# Communication.net
KiCad netlist of a schematic drawn in Altium Designer
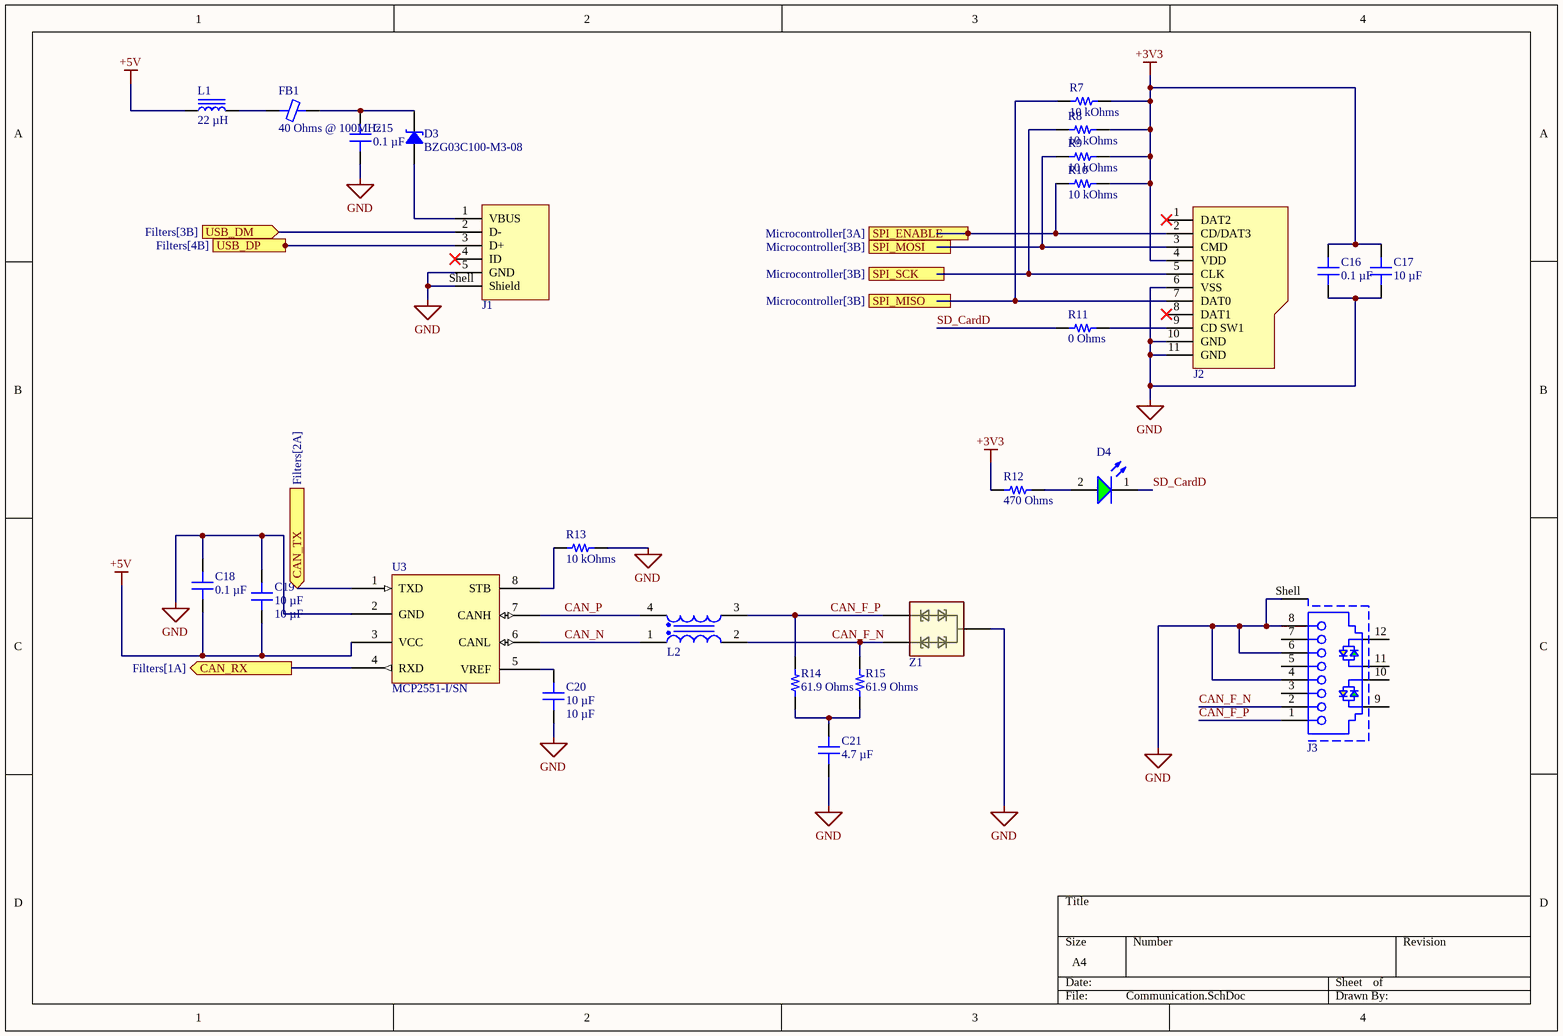
[diagram p0: Communication.SchDoc]

(export (version "E")
  (design (tool "Eeschema 10.0.6"))
  (components
    (comp (ref "C15")
      (value "0.1 µF")
      (footprint "CAP 0805_2012")
      (description "CAP CER 0.1UF 50V X7R 0805")
      (fields (field (name "PART NUMBER") "CC0805MRX7R9BB104") (field (name "MANUFACTURER") "Yageo"))
      (libsource (lib "Celestial Altium Library - altium_library (2)") (part "Capacitor"))
    )
    (comp (ref "C16")
      (value "0.1 µF")
      (footprint "CAP 0805_2012")
      (description "CAP CER 0.1UF 50V X7R 0805")
      (fields (field (name "PART NUMBER") "CC0805MRX7R9BB104") (field (name "MANUFACTURER") "Yageo"))
      (libsource (lib "Celestial Altium Library - altium_library (2)") (part "Capacitor"))
    )
    (comp (ref "C17")
      (value "10 µF")
      (footprint "CAP 0805_2012")
      (description "CAP CER 10UF 10V X7S 0805")
      (fields
        (field (name "PART NUMBER") "CL21Y106KPQVPNE")
        (field (name "MANUFACTURER") "Samsung Electro-Mechanics")
      )
      (libsource (lib "Celestial Altium Library - altium_library (2)") (part "Capacitor"))
    )
    (comp (ref "C18")
      (value "0.1 µF")
      (footprint "CAP 0805_2012")
      (description "CAP CER 0.1UF 50V X7R 0805")
      (fields (field (name "PART NUMBER") "CC0805MRX7R9BB104") (field (name "MANUFACTURER") "Yageo"))
      (libsource (lib "Celestial Altium Library - altium_library (2)") (part "Capacitor"))
    )
    (comp (ref "C19")
      (value "10 µF")
      (footprint "CAP 0805_2012")
      (description "CAP CER 10UF 10V X7S 0805")
      (fields (field (name "PART NUMBER") "CL21Y106KPQVPNE") (field (name "ALTIUM_VALUE") "10 µF"))
      (libsource (lib "Celestial Altium Library - altium_library (2)") (part "Capacitor"))
    )
    (comp (ref "C20")
      (value "10 µF")
      (footprint "CAP 0805_2012")
      (description "CAP CER 10UF 10V X7S 0805")
      (fields (field (name "PART NUMBER") "CL21Y106KPQVPNE") (field (name "ALTIUM_VALUE") "10 µF"))
      (libsource (lib "Celestial Altium Library - altium_library (2)") (part "Capacitor"))
    )
    (comp (ref "C21")
      (value "4.7 µF")
      (footprint "CAP 0805_2012")
      (description "CAP CER 4.7UF 25V X7R 0805")
      (fields
        (field (name "PART NUMBER") "CL21B475KAFNNNE")
        (field (name "MANUFACTURER") "Samsung Electro-Mechanics")
      )
      (libsource (lib "Celestial Altium Library - altium_library (2)") (part "Capacitor"))
    )
    (comp (ref "D3")
      (value "BZG03C100-M3-08")
      (footprint "DO214AC SMA")
      (description "DIODE ZENER 100V 1.25W DO214AC")
      (fields
        (field (name "MANUFACTURER") "Vishay Semiconductor Diodes Division")
        (field (name "TOLERANCE") "±6%")
      )
      (libsource (lib "Celestial Altium Library - altium_library (2)") (part "Diode Zener"))
    )
    (comp (ref "D4")
      (value "Green, 3.2V, 140°")
      (footprint "WL-SMCW_0805_150080xx75000")
      (description "WL-SMCW Mono-color Chip LED Waterclear, size 0805, Green, 3.2V, 140°")
      (fields
        (field (name "MANUFACTURER PART NUMBER") "150080GS75000")
        (field (name "MANUFACTURER") "Wurth Elektronik")
      )
      (libsource (lib "WE - Optoelectronic Components") (part "LED_Green_2A-1K"))
    )
    (comp (ref "FB1")
      (value "40 Ohms @ 100MHz")
      (footprint "FER 0805_2012")
      (description "FERRITE BEAD 40 OHM 0805 1LN")
      (fields (field (name "PART NUMBER") "ILBB0805ER400V") (field (name "MANUFACTURER") "Vishay Dale"))
      (libsource (lib "Celestial Altium Library - altium_library (2)") (part "Ferrite Chip"))
    )
    (comp (ref "J1")
      (value "629105150521")
      (footprint "629105150521")
      (description "WR-COM Micro USB 2.0 SMT Type B Horizontal 5 Contacts High Current")
      (fields (field (name "MANUFACTURER") "Wurth Elektronik"))
      (libsource (lib "WE - Electromechanical Components") (part "Micro USB 2.0_Type B_Receptacle_1 Port"))
    )
    (comp (ref "J2")
      (value "693071030811")
      (footprint "693071030811")
      (description "WR-CRD Micro SD Card Connector Push & Push")
      (fields (field (name "MANUFACTURER") "Wurth Elektronik"))
      (libsource (lib "WE - Electromechanical Components") (part "693071030811"))
    )
    (comp (ref "J3")
      (value "615008142121")
      (footprint "615008142121")
      (description "WR-MJ Modular Jack THT Horizontal Shielded 8P8C Tab Up")
      (fields (field (name "MANUFACTURER") "Wurth Elektronik"))
      (libsource (lib "WE - Electromechanical Components") (part "8P8C - 1 Port - Shielded - Bipolar Y/G - 615008142121"))
    )
    (comp (ref "L1")
      (value "22 µH")
      (footprint "IND 0806_2016")
      (description "FIXED IND 22UH 310MA 1 OHM SMD")
      (fields (field (name "PART NUMBER") "LSQPB201616T220M") (field (name "MANUFACTURER") "Taiyo Yuden"))
      (libsource (lib "Celestial Altium Library - altium_library (2)") (part "Inductor"))
    )
    (comp (ref "L2")
      (value "5000Ohm")
      (footprint "WE-CNSW_1812")
      (description "WE-CNSW SMT Common Mode Line Filter, size 1812, 5000Ohm, 100uH, 60V")
      (fields
        (field (name "MANUFACTURER PART NUMBER") "744235101")
        (field (name "MANUFACTURER") "Wurth Elektronik")
      )
      (libsource (lib "WE - Passive Components") (part "WE-CNSW"))
    )
    (comp (ref "R7")
      (value "10 kOhms")
      (footprint "RES 0805_2012")
      (description "RES SMD 10K OHM 0.1% 1/4W 0805")
      (fields
        (field (name "PART NUMBER") "2176093-5")
        (field (name "MANUFACTURER") "TE Connectivity Passive Product")
      )
      (libsource (lib "Celestial Altium Library - altium_library (2)") (part "Resistor"))
    )
    (comp (ref "R8")
      (value "10 kOhms")
      (footprint "RES 0805_2012")
      (description "RES SMD 10K OHM 0.1% 1/4W 0805")
      (fields
        (field (name "PART NUMBER") "2176093-5")
        (field (name "MANUFACTURER") "TE Connectivity Passive Product")
      )
      (libsource (lib "Celestial Altium Library - altium_library (2)") (part "Resistor"))
    )
    (comp (ref "R9")
      (value "10 kOhms")
      (footprint "RES 0805_2012")
      (description "RES SMD 10K OHM 0.1% 1/4W 0805")
      (fields
        (field (name "PART NUMBER") "2176093-5")
        (field (name "MANUFACTURER") "TE Connectivity Passive Product")
      )
      (libsource (lib "Celestial Altium Library - altium_library (2)") (part "Resistor"))
    )
    (comp (ref "R10")
      (value "10 kOhms")
      (footprint "RES 0805_2012")
      (description "RES SMD 10K OHM 0.1% 1/4W 0805")
      (fields
        (field (name "PART NUMBER") "2176093-5")
        (field (name "MANUFACTURER") "TE Connectivity Passive Product")
      )
      (libsource (lib "Celestial Altium Library - altium_library (2)") (part "Resistor"))
    )
    (comp (ref "R11")
      (value "0 Ohms")
      (footprint "RES 0805_2012")
      (description "RES 0 OHM JUMPER 0805")
      (fields (field (name "PART NUMBER") "5107") (field (name "MANUFACTURER") "Keystone Electronics"))
      (libsource (lib "Celestial Altium Library - altium_library (2)") (part "Resistor"))
    )
    (comp (ref "R12")
      (value "470 Ohms")
      (footprint "RES 0805_2012")
      (description "3430 A2 1% 470R 100PPM 1K RL")
      (fields
        (field (name "PART NUMBER") "3430A2F470RTDF")
        (field (name "MANUFACTURER") "TE Connectivity Passive Product")
      )
      (libsource (lib "Celestial Altium Library - altium_library (2)") (part "Resistor"))
    )
    (comp (ref "R13")
      (value "10 kOhms")
      (footprint "RES 0805_2012")
      (description "RES SMD 10K OHM 0.1% 1/4W 0805")
      (fields
        (field (name "PART NUMBER") "2176093-5")
        (field (name "MANUFACTURER") "TE Connectivity Passive Product")
      )
      (libsource (lib "Celestial Altium Library - altium_library (2)") (part "Resistor"))
    )
    (comp (ref "R14")
      (value "61.9 Ohms")
      (footprint "RES 0805_2012")
      (description "RES SMD 61.9 OHM 0.1% 1/4W 0805")
      (fields
        (field (name "PART NUMBER") "2176091-4")
        (field (name "MANUFACTURER") "TE Connectivity Passive Product")
      )
      (libsource (lib "Celestial Altium Library - altium_library (2)") (part "Resistor"))
    )
    (comp (ref "R15")
      (value "61.9 Ohms")
      (footprint "RES 0805_2012")
      (description "RES SMD 61.9 OHM 0.1% 1/4W 0805")
      (fields
        (field (name "PART NUMBER") "2176091-4")
        (field (name "MANUFACTURER") "TE Connectivity Passive Product")
      )
      (libsource (lib "Celestial Altium Library - altium_library (2)") (part "Resistor"))
    )
    (comp (ref "U3")
      (value "MCP2551")
      (footprint "MCP2551T-I/SN")
      (description "MCP2551 CAN Transreciever 8Mbit/sn")
      (fields (field (name "SUPPLIER PART NUMBER 1") "MCP2551-I/SN"))
      (libsource (lib "Schlib1") (part "MCP2551"))
    )
    (comp (ref "Z1")
      (value "PESD2CAN,215")
      (footprint "SOT95P230X110-3N")
      (description "Zener Diode")
      (fields
        (field (name "MOUSER PART NUMBER") "771-PESD2CAN-T/R")
        (field (name "RS PART NUMBER") "0508462")
      )
      (libsource (lib "Schlib1") (part "PESD2CAN,215"))
    )
  )
  (nets
    (net (code "1") (name "+3V3") (class "Default")
      (node (ref "C16") (pin "2") (pinfunction "2_2") (pintype "passive"))
      (node (ref "C17") (pin "2") (pinfunction "2_2") (pintype "passive"))
      (node (ref "J2") (pin "4") (pinfunction "VDD_4") (pintype "passive"))
      (node (ref "R10") (pin "2") (pinfunction "2_2") (pintype "passive"))
      (node (ref "R12") (pin "1") (pinfunction "1_1") (pintype "passive"))
      (node (ref "R7") (pin "2") (pinfunction "2_2") (pintype "passive"))
      (node (ref "R8") (pin "2") (pinfunction "2_2") (pintype "passive"))
      (node (ref "R9") (pin "2") (pinfunction "2_2") (pintype "passive"))
    )
    (net (code "2") (name "+5V") (class "Default")
      (node (ref "C18") (pin "2") (pinfunction "2_2") (pintype "passive"))
      (node (ref "C19") (pin "1") (pinfunction "1_1") (pintype "passive"))
      (node (ref "L1") (pin "1") (pinfunction "1_1") (pintype "passive"))
      (node (ref "U3") (pin "3") (pinfunction "VCC_3") (pintype "passive"))
    )
    (net (code "3") (name "/CAN_F_N") (class "Default")
      (node (ref "J3") (pin "2") (pinfunction "2_2") (pintype "passive"))
      (node (ref "L2") (pin "2") (pinfunction "2_2") (pintype "passive"))
      (node (ref "R15") (pin "2") (pinfunction "2_2") (pintype "passive"))
      (node (ref "Z1") (pin "2") (pinfunction "2_2") (pintype "passive"))
    )
    (net (code "4") (name "/CAN_F_P") (class "Default")
      (node (ref "J3") (pin "1") (pinfunction "1_1") (pintype "passive"))
      (node (ref "L2") (pin "3") (pinfunction "3_3") (pintype "passive"))
      (node (ref "R14") (pin "2") (pinfunction "2_2") (pintype "passive"))
      (node (ref "Z1") (pin "1") (pinfunction "1_1") (pintype "passive"))
    )
    (net (code "5") (name "/CAN_N") (class "Default")
      (node (ref "L2") (pin "1") (pinfunction "1_1") (pintype "passive"))
      (node (ref "U3") (pin "6") (pinfunction "CANL_6") (pintype "bidirectional"))
    )
    (net (code "6") (name "/CAN_P") (class "Default")
      (node (ref "L2") (pin "4") (pinfunction "4_4") (pintype "passive"))
      (node (ref "U3") (pin "7") (pinfunction "CANH_7") (pintype "bidirectional"))
    )
    (net (code "7") (name "/CAN_RX") (class "Default")
      (node (ref "U3") (pin "4") (pinfunction "RXD_4") (pintype "output"))
    )
    (net (code "8") (name "/CAN_TX") (class "Default")
      (node (ref "U3") (pin "1") (pinfunction "TXD_1") (pintype "input"))
    )
    (net (code "9") (name "/SD_CardD") (class "Default")
      (node (ref "D4") (pin "1") (pinfunction "K_1") (pintype "passive"))
      (node (ref "R11") (pin "1") (pinfunction "1_1") (pintype "passive"))
    )
    (net (code "10") (name "/SPI_ENABLE") (class "Default")
      (node (ref "J2") (pin "2") (pinfunction "CD/DAT3_2") (pintype "passive"))
      (node (ref "R10") (pin "1") (pinfunction "1_1") (pintype "passive"))
    )
    (net (code "11") (name "/SPI_MISO") (class "Default")
      (node (ref "J2") (pin "7") (pinfunction "DAT0_7") (pintype "passive"))
      (node (ref "R7") (pin "1") (pinfunction "1_1") (pintype "passive"))
    )
    (net (code "12") (name "/SPI_MOSI") (class "Default")
      (node (ref "J2") (pin "3") (pinfunction "CMD_3") (pintype "passive"))
      (node (ref "R9") (pin "1") (pinfunction "1_1") (pintype "passive"))
    )
    (net (code "13") (name "/SPI_SCK") (class "Default")
      (node (ref "J2") (pin "5") (pinfunction "CLK_5") (pintype "passive"))
      (node (ref "R8") (pin "1") (pinfunction "1_1") (pintype "passive"))
    )
    (net (code "14") (name "/USB_DM") (class "Default")
      (node (ref "J1") (pin "2") (pinfunction "D-_2") (pintype "passive"))
    )
    (net (code "15") (name "/USB_DP") (class "Default")
      (node (ref "J1") (pin "3") (pinfunction "D+_3") (pintype "passive"))
    )
    (net (code "16") (name "GND") (class "Default")
      (node (ref "C15") (pin "1") (pinfunction "1_1") (pintype "passive"))
      (node (ref "C16") (pin "1") (pinfunction "1_1") (pintype "passive"))
      (node (ref "C17") (pin "1") (pinfunction "1_1") (pintype "passive"))
      (node (ref "C18") (pin "1") (pinfunction "1_1") (pintype "passive"))
      (node (ref "C19") (pin "2") (pinfunction "2_2") (pintype "passive"))
      (node (ref "C20") (pin "1") (pinfunction "1_1") (pintype "passive"))
      (node (ref "C21") (pin "1") (pinfunction "1_1") (pintype "passive"))
      (node (ref "J1") (pin "5") (pinfunction "GND_5") (pintype "passive"))
      (node (ref "J1") (pin "Shell") (pinfunction "Shield_Shell") (pintype "passive"))
      (node (ref "J2") (pin "10") (pinfunction "GND_10") (pintype "passive"))
      (node (ref "J2") (pin "11") (pinfunction "GND_11") (pintype "passive"))
      (node (ref "J2") (pin "6") (pinfunction "VSS_6") (pintype "passive"))
      (node (ref "J3") (pin "4") (pinfunction "4_4") (pintype "passive"))
      (node (ref "J3") (pin "6") (pinfunction "6_6") (pintype "passive"))
      (node (ref "J3") (pin "8") (pinfunction "8_8") (pintype "passive"))
      (node (ref "J3") (pin "Shell") (pinfunction "Shell_Shell") (pintype "passive"))
      (node (ref "R13") (pin "2") (pinfunction "2_2") (pintype "passive"))
      (node (ref "U3") (pin "2") (pinfunction "GND_2") (pintype "passive"))
      (node (ref "Z1") (pin "3") (pinfunction "3_3") (pintype "passive"))
    )
    (net (code "17") (name "Net-(C15-Pad2)") (class "Default")
      (node (ref "C15") (pin "2") (pinfunction "2_2") (pintype "passive"))
      (node (ref "D3") (pin "2") (pinfunction "2_2") (pintype "passive"))
      (node (ref "FB1") (pin "2") (pinfunction "2_2") (pintype "passive"))
    )
    (net (code "18") (name "Net-(C21-Pad2)") (class "Default")
      (node (ref "C21") (pin "2") (pinfunction "2_2") (pintype "passive"))
      (node (ref "R14") (pin "1") (pinfunction "1_1") (pintype "passive"))
      (node (ref "R15") (pin "1") (pinfunction "1_1") (pintype "passive"))
    )
    (net (code "19") (name "Net-(D4-A)") (class "Default")
      (node (ref "D4") (pin "2") (pinfunction "A_2") (pintype "passive"))
      (node (ref "R12") (pin "2") (pinfunction "2_2") (pintype "passive"))
    )
    (net (code "20") (name "Net-(FB1-Pad1)") (class "Default")
      (node (ref "FB1") (pin "1") (pinfunction "1_1") (pintype "passive"))
      (node (ref "L1") (pin "2") (pinfunction "2_2") (pintype "passive"))
    )
    (net (code "21") (name "Net-(J1-VBUS)") (class "Default")
      (node (ref "D3") (pin "1") (pinfunction "1_1") (pintype "passive"))
      (node (ref "J1") (pin "1") (pinfunction "VBUS_1") (pintype "passive"))
    )
    (net (code "22") (name "Net-(J2-CD_SW1)") (class "Default")
      (node (ref "J2") (pin "9") (pinfunction "CD_SW1_9") (pintype "passive"))
      (node (ref "R11") (pin "2") (pinfunction "2_2") (pintype "passive"))
    )
    (net (code "23") (name "Net-(U3-STB)") (class "Default")
      (node (ref "R13") (pin "1") (pinfunction "1_1") (pintype "passive"))
      (node (ref "U3") (pin "8") (pinfunction "STB_8") (pintype "passive"))
    )
    (net (code "24") (name "Net-(U3-VREF)") (class "Default")
      (node (ref "C20") (pin "2") (pinfunction "2_2") (pintype "passive"))
      (node (ref "U3") (pin "5") (pinfunction "VREF_5") (pintype "passive"))
    )
    (net (code "25") (name "unconnected-(J1-ID-Pad4)") (class "Default")
      (node (ref "J1") (pin "4") (pinfunction "ID_4") (pintype "passive+no_connect"))
    )
    (net (code "26") (name "unconnected-(J2-DAT1-Pad8)") (class "Default")
      (node (ref "J2") (pin "8") (pinfunction "DAT1_8") (pintype "passive+no_connect"))
    )
    (net (code "27") (name "unconnected-(J2-DAT2-Pad1)") (class "Default")
      (node (ref "J2") (pin "1") (pinfunction "DAT2_1") (pintype "passive+no_connect"))
    )
    (net (code "28") (name "unconnected-(J3-Pad3)") (class "Default")
      (node (ref "J3") (pin "3") (pinfunction "3_3") (pintype "passive"))
    )
    (net (code "29") (name "unconnected-(J3-Pad5)") (class "Default")
      (node (ref "J3") (pin "5") (pinfunction "5_5") (pintype "passive"))
    )
    (net (code "30") (name "unconnected-(J3-Pad7)") (class "Default")
      (node (ref "J3") (pin "7") (pinfunction "7_7") (pintype "passive"))
    )
    (net (code "31") (name "unconnected-(J3-Pad9)") (class "Default")
      (node (ref "J3") (pin "9") (pinfunction "9_9") (pintype "passive"))
    )
    (net (code "32") (name "unconnected-(J3-Pad10)") (class "Default")
      (node (ref "J3") (pin "10") (pinfunction "10_10") (pintype "passive"))
    )
    (net (code "33") (name "unconnected-(J3-Pad11)") (class "Default")
      (node (ref "J3") (pin "11") (pinfunction "11_11") (pintype "passive"))
    )
    (net (code "34") (name "unconnected-(J3-Pad12)") (class "Default")
      (node (ref "J3") (pin "12") (pinfunction "12_12") (pintype "passive"))
    )
  )
)
